# MoWeSta-Minimalist.net
KiCad netlist of a schematic drawn in EAGLE
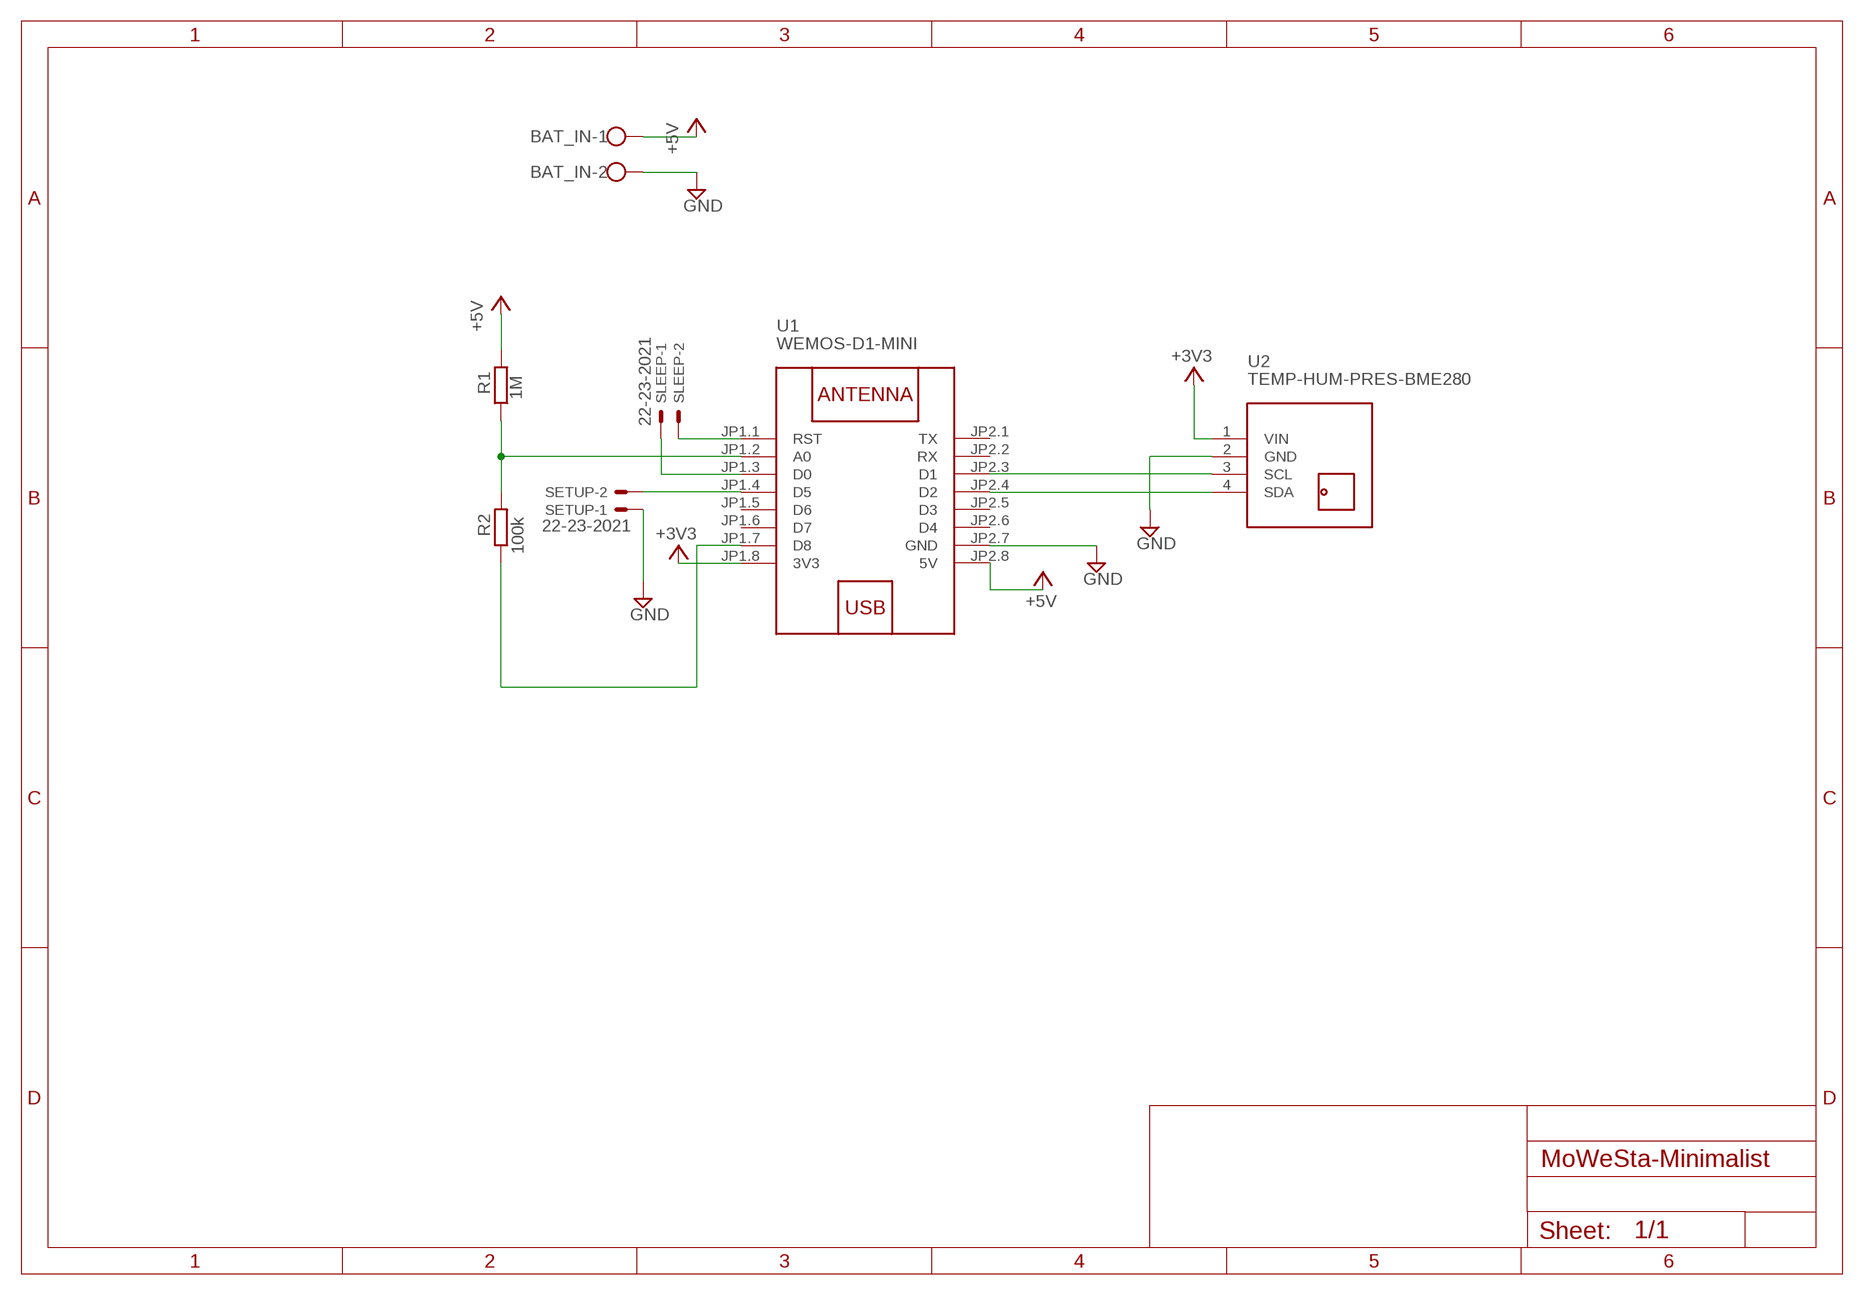
[diagram p0: schematic, sheet 1]

(export (version "E")
  (design (tool "Eeschema 10.0.6"))
  (components
    (comp (ref "BAT_IN")
      (value "W237-102")
      (footprint "eagle-import:W237-102")
      (fields (field (name "MPN") "237-102"))
      (libsource (lib "eagle-import") (part "W237-102"))
    )
    (comp (ref "R1")
      (value "1M")
      (footprint "eagle-import:0204_7")
      (libsource (lib "eagle-import") (part "R-EU_0204/7"))
    )
    (comp (ref "R2")
      (value "100k")
      (footprint "eagle-import:0204_7")
      (libsource (lib "eagle-import") (part "R-EU_0204/7"))
    )
    (comp (ref "SETUP")
      (value "22-23-2021")
      (footprint "eagle-import:22-23-2021")
      (fields (field (name "MF") "MOLEX"))
      (libsource (lib "eagle-import") (part "22-23-2021"))
    )
    (comp (ref "SLEEP")
      (value "22-23-2021")
      (footprint "eagle-import:22-23-2021")
      (fields (field (name "MF") "MOLEX"))
      (libsource (lib "eagle-import") (part "22-23-2021"))
    )
    (comp (ref "U1")
      (value "WEMOS-D1-MINI")
      (footprint "eagle-import:WEMOS-D1-MINI")
      (libsource (lib "eagle-import") (part "WEMOS-D1-MINI"))
    )
    (comp (ref "U2")
      (value "TEMP-HUM-PRES-BME280")
      (footprint "eagle-import:TEMP-HUM-PRES-BME280")
      (libsource (lib "eagle-import") (part "TEMP-HUM-PRES-BME280"))
    )
  )
  (nets
    (net (code "1") (name "+3V3") (class "Default")
      (node (ref "U1") (pin "JP1.8") (pinfunction "3V3_JP1.8") (pintype "power_in"))
      (node (ref "U2") (pin "1") (pinfunction "VIN_1") (pintype "power_in"))
    )
    (net (code "2") (name "+5V") (class "Default")
      (node (ref "BAT_IN") (pin "1") (pinfunction "KL_1") (pintype "passive"))
      (node (ref "R1") (pin "2") (pinfunction "2_2") (pintype "passive"))
      (node (ref "U1") (pin "JP2.8") (pinfunction "5V_JP2.8") (pintype "power_in"))
    )
    (net (code "3") (name "GND") (class "Default")
      (node (ref "BAT_IN") (pin "2") (pinfunction "KL_2") (pintype "passive"))
      (node (ref "SETUP") (pin "1") (pinfunction "S_1") (pintype "passive"))
      (node (ref "U1") (pin "JP2.7") (pinfunction "GND_JP2.7") (pintype "power_in"))
      (node (ref "U2") (pin "2") (pinfunction "GND_2") (pintype "power_in"))
    )
    (net (code "4") (name "Net-(SETUPB-S)") (class "Default")
      (node (ref "SETUP") (pin "2") (pinfunction "S_2") (pintype "passive"))
      (node (ref "U1") (pin "JP1.4") (pinfunction "D5_JP1.4") (pintype "bidirectional"))
    )
    (net (code "5") (name "Net-(SLEEPA-S)") (class "Default")
      (node (ref "SLEEP") (pin "1") (pinfunction "S_1") (pintype "passive"))
      (node (ref "U1") (pin "JP1.3") (pinfunction "D0_JP1.3") (pintype "bidirectional"))
    )
    (net (code "6") (name "Net-(SLEEPB-S)") (class "Default")
      (node (ref "SLEEP") (pin "2") (pinfunction "S_2") (pintype "passive"))
      (node (ref "U1") (pin "JP1.1") (pinfunction "RST_JP1.1") (pintype "bidirectional"))
    )
    (net (code "7") (name "Net-(U1-A0)") (class "Default")
      (node (ref "R1") (pin "1") (pinfunction "1_1") (pintype "passive"))
      (node (ref "R2") (pin "2") (pinfunction "2_2") (pintype "passive"))
      (node (ref "U1") (pin "JP1.2") (pinfunction "A0_JP1.2") (pintype "bidirectional"))
    )
    (net (code "8") (name "Net-(U1-D1)") (class "Default")
      (node (ref "U1") (pin "JP2.3") (pinfunction "D1_JP2.3") (pintype "bidirectional"))
      (node (ref "U2") (pin "3") (pinfunction "SCL_3") (pintype "bidirectional"))
    )
    (net (code "9") (name "Net-(U1-D2)") (class "Default")
      (node (ref "U1") (pin "JP2.4") (pinfunction "D2_JP2.4") (pintype "bidirectional"))
      (node (ref "U2") (pin "4") (pinfunction "SDA_4") (pintype "bidirectional"))
    )
    (net (code "10") (name "Net-(U1-D8)") (class "Default")
      (node (ref "R2") (pin "1") (pinfunction "1_1") (pintype "passive"))
      (node (ref "U1") (pin "JP1.7") (pinfunction "D8_JP1.7") (pintype "bidirectional"))
    )
    (net (code "11") (name "unconnected-(U1-D3-PadJP2.5)") (class "Default")
      (node (ref "U1") (pin "JP2.5") (pinfunction "D3_JP2.5") (pintype "bidirectional"))
    )
    (net (code "12") (name "unconnected-(U1-D4-PadJP2.6)") (class "Default")
      (node (ref "U1") (pin "JP2.6") (pinfunction "D4_JP2.6") (pintype "bidirectional"))
    )
    (net (code "13") (name "unconnected-(U1-D6-PadJP1.5)") (class "Default")
      (node (ref "U1") (pin "JP1.5") (pinfunction "D6_JP1.5") (pintype "bidirectional"))
    )
    (net (code "14") (name "unconnected-(U1-D7-PadJP1.6)") (class "Default")
      (node (ref "U1") (pin "JP1.6") (pinfunction "D7_JP1.6") (pintype "bidirectional"))
    )
    (net (code "15") (name "unconnected-(U1-RX-PadJP2.2)") (class "Default")
      (node (ref "U1") (pin "JP2.2") (pinfunction "RX_JP2.2") (pintype "bidirectional"))
    )
    (net (code "16") (name "unconnected-(U1-TX-PadJP2.1)") (class "Default")
      (node (ref "U1") (pin "JP2.1") (pinfunction "TX_JP2.1") (pintype "bidirectional"))
    )
  )
)
